# version3.net
KiCad netlist of a schematic drawn in EAGLE
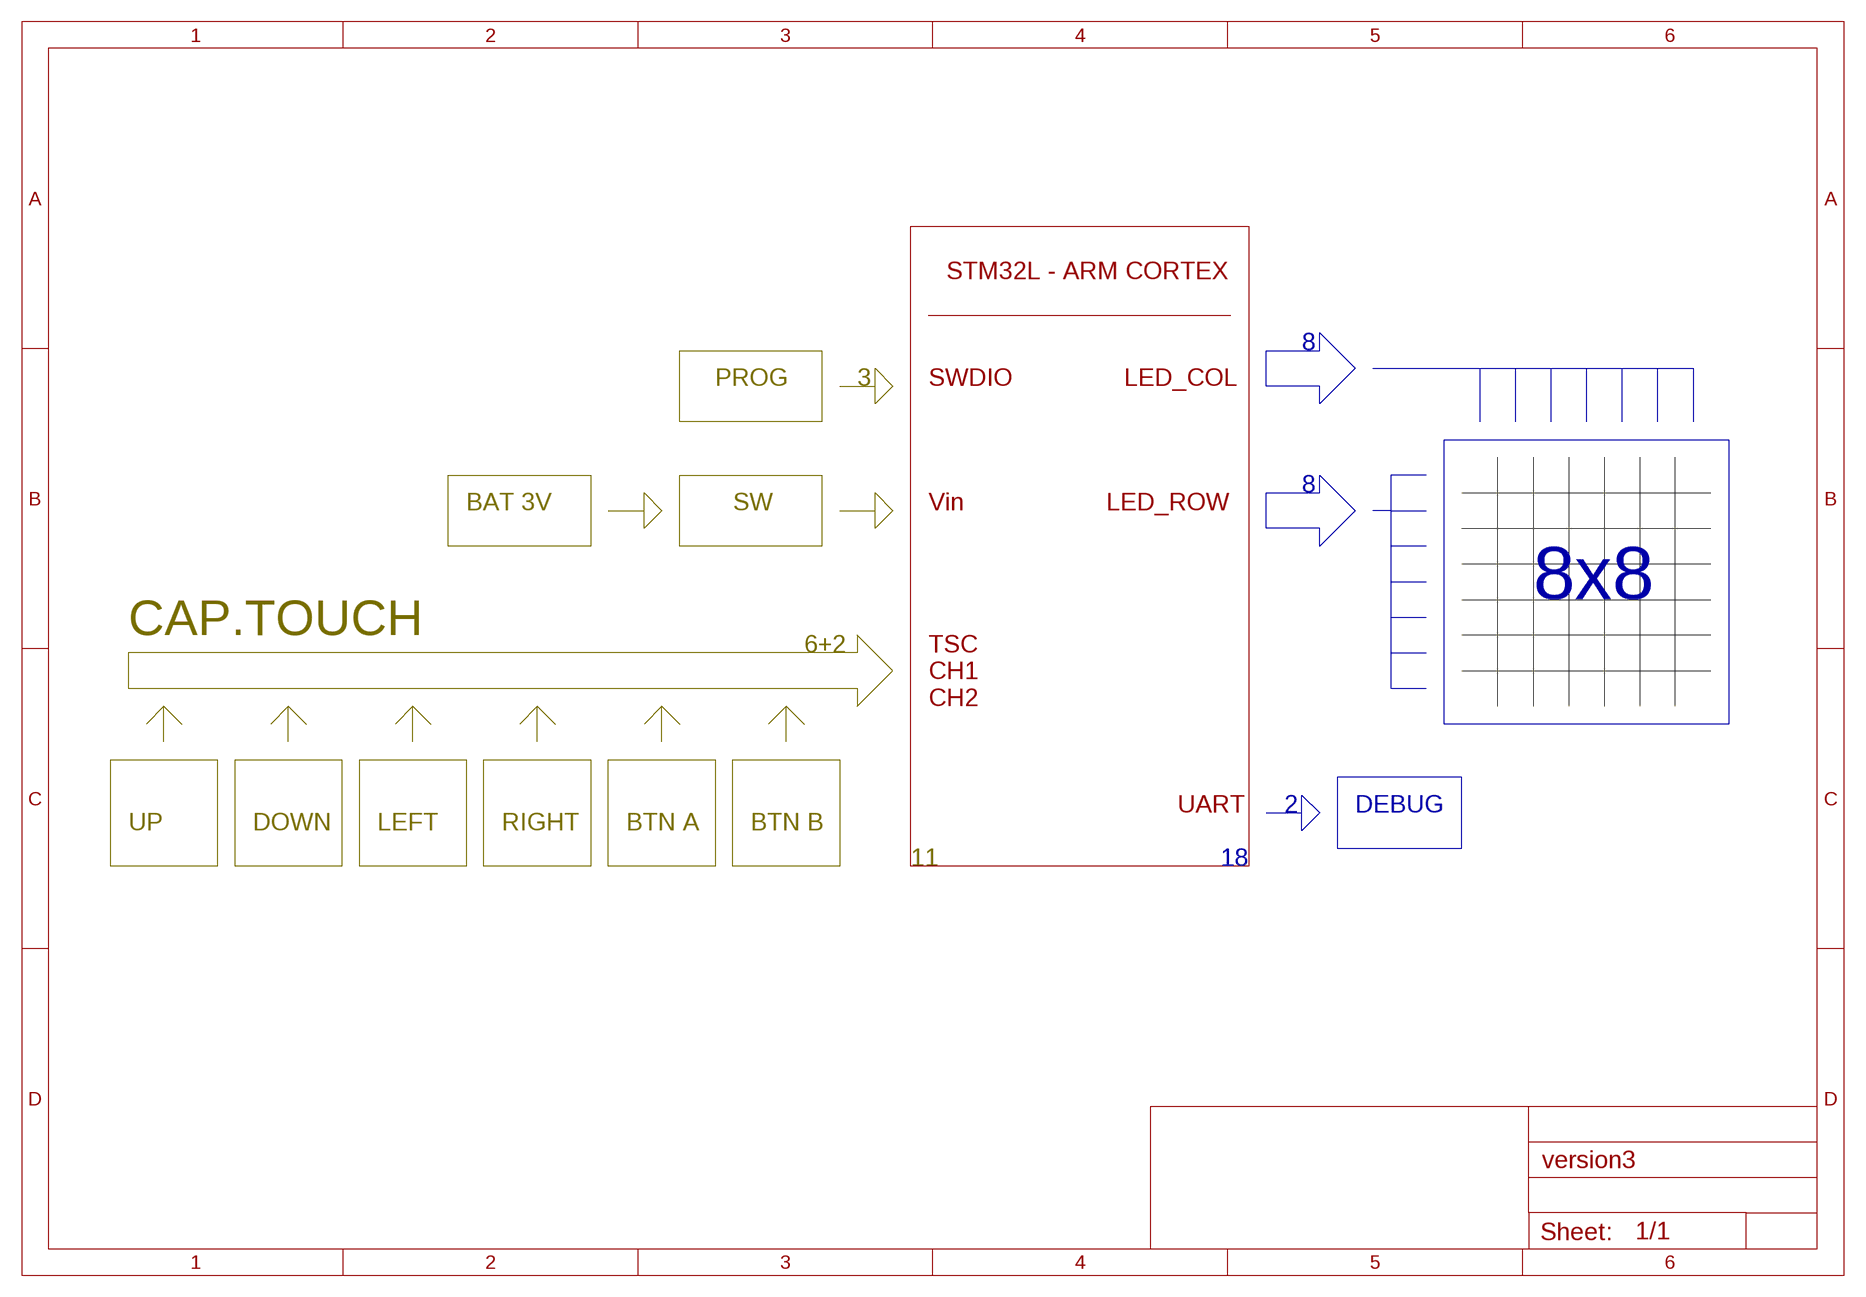
[diagram p0: schematic, sheet 1, part 1 of 2]
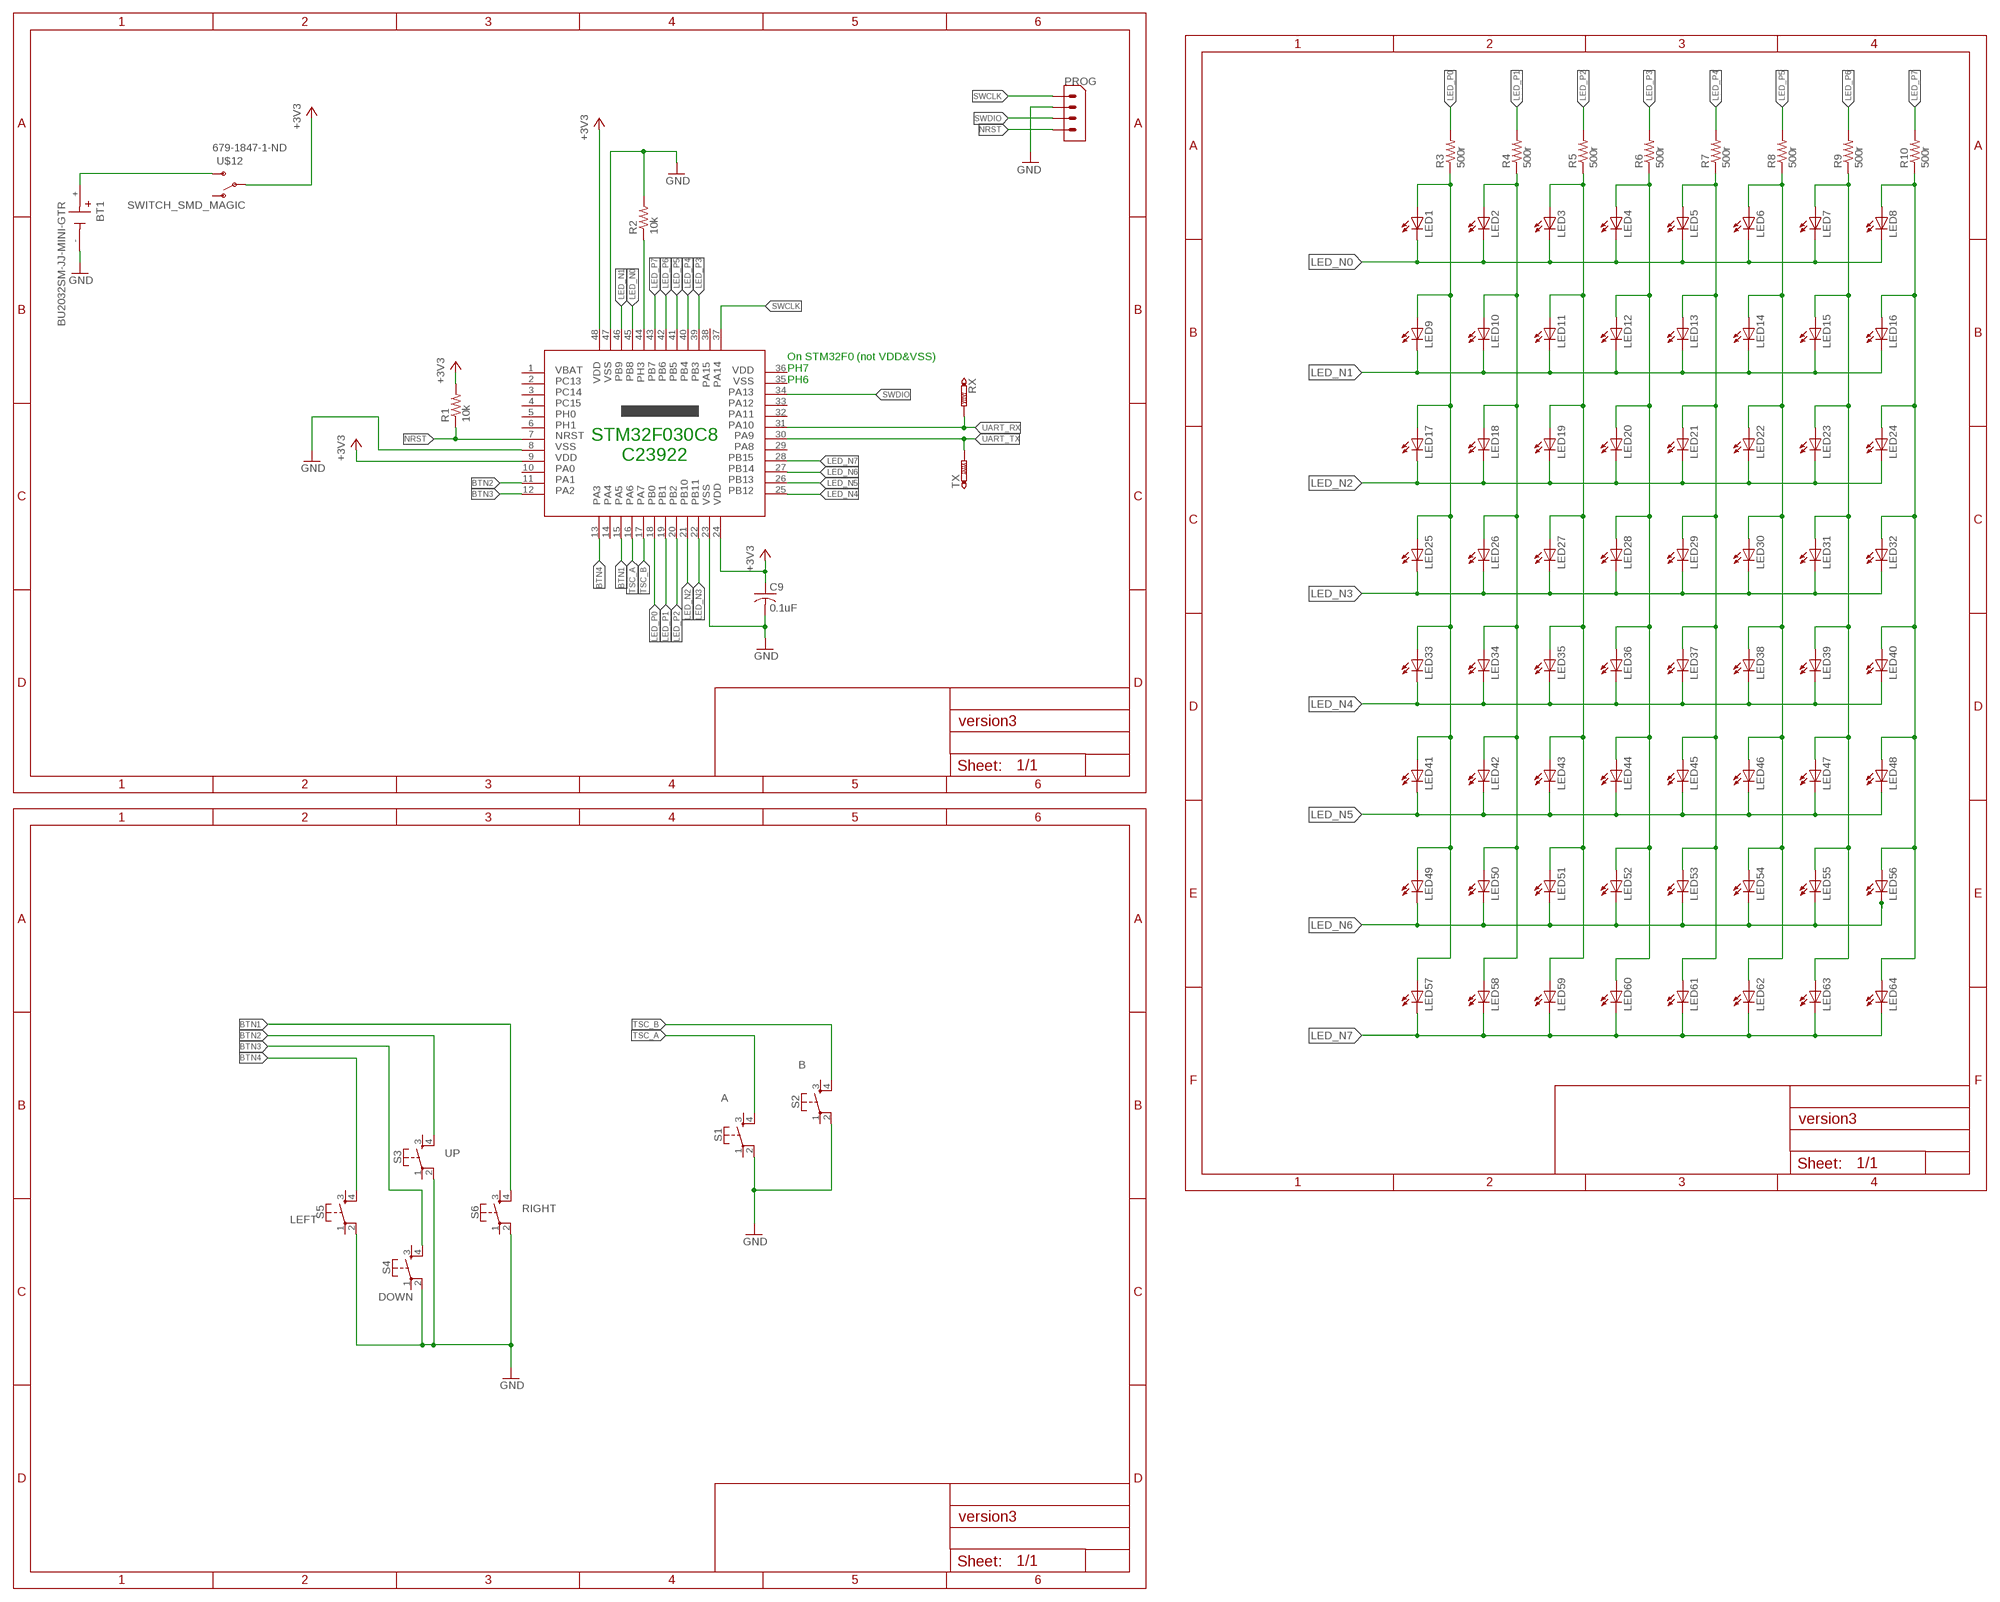
[diagram p1: schematic, sheet 1, part 2 of 2]

(export (version "E")
  (design (tool "Eeschema 10.0.6"))
  (components
    (comp (ref "BT1")
      (value "BU2032SM-JJ-MINI-GTR")
      (footprint "eagle-import:BAT_BU2032SM-JJ-MINI-GTR")
      (fields (field (name "MF") "MPD _Memory"))
      (libsource (lib "eagle-import") (part "BU2032SM-JJ-MINI-GTR"))
    )
    (comp (ref "C9")
      (value "0.1uF")
      (footprint "eagle-import:C0603")
      (libsource (lib "eagle-import") (part "C-USC0603"))
    )
    (comp (ref "LED1")
      (value "LEDCHIP-LED0603")
      (footprint "eagle-import:CHIP-LED0603")
      (libsource (lib "eagle-import") (part "LEDCHIP-LED0603"))
    )
    (comp (ref "LED2")
      (value "LEDCHIP-LED0603")
      (footprint "eagle-import:CHIP-LED0603")
      (libsource (lib "eagle-import") (part "LEDCHIP-LED0603"))
    )
    (comp (ref "LED3")
      (value "LEDCHIP-LED0603")
      (footprint "eagle-import:CHIP-LED0603")
      (libsource (lib "eagle-import") (part "LEDCHIP-LED0603"))
    )
    (comp (ref "LED4")
      (value "LEDCHIP-LED0603")
      (footprint "eagle-import:CHIP-LED0603")
      (libsource (lib "eagle-import") (part "LEDCHIP-LED0603"))
    )
    (comp (ref "LED5")
      (value "LEDCHIP-LED0603")
      (footprint "eagle-import:CHIP-LED0603")
      (libsource (lib "eagle-import") (part "LEDCHIP-LED0603"))
    )
    (comp (ref "LED6")
      (value "LEDCHIP-LED0603")
      (footprint "eagle-import:CHIP-LED0603")
      (libsource (lib "eagle-import") (part "LEDCHIP-LED0603"))
    )
    (comp (ref "LED7")
      (value "LEDCHIP-LED0603")
      (footprint "eagle-import:CHIP-LED0603")
      (libsource (lib "eagle-import") (part "LEDCHIP-LED0603"))
    )
    (comp (ref "LED8")
      (value "LEDCHIP-LED0603")
      (footprint "eagle-import:CHIP-LED0603")
      (libsource (lib "eagle-import") (part "LEDCHIP-LED0603"))
    )
    (comp (ref "LED9")
      (value "LEDCHIP-LED0603")
      (footprint "eagle-import:CHIP-LED0603")
      (libsource (lib "eagle-import") (part "LEDCHIP-LED0603"))
    )
    (comp (ref "LED10")
      (value "LEDCHIP-LED0603")
      (footprint "eagle-import:CHIP-LED0603")
      (libsource (lib "eagle-import") (part "LEDCHIP-LED0603"))
    )
    (comp (ref "LED11")
      (value "LEDCHIP-LED0603")
      (footprint "eagle-import:CHIP-LED0603")
      (libsource (lib "eagle-import") (part "LEDCHIP-LED0603"))
    )
    (comp (ref "LED12")
      (value "LEDCHIP-LED0603")
      (footprint "eagle-import:CHIP-LED0603")
      (libsource (lib "eagle-import") (part "LEDCHIP-LED0603"))
    )
    (comp (ref "LED13")
      (value "LEDCHIP-LED0603")
      (footprint "eagle-import:CHIP-LED0603")
      (libsource (lib "eagle-import") (part "LEDCHIP-LED0603"))
    )
    (comp (ref "LED14")
      (value "LEDCHIP-LED0603")
      (footprint "eagle-import:CHIP-LED0603")
      (libsource (lib "eagle-import") (part "LEDCHIP-LED0603"))
    )
    (comp (ref "LED15")
      (value "LEDCHIP-LED0603")
      (footprint "eagle-import:CHIP-LED0603")
      (libsource (lib "eagle-import") (part "LEDCHIP-LED0603"))
    )
    (comp (ref "LED16")
      (value "LEDCHIP-LED0603")
      (footprint "eagle-import:CHIP-LED0603")
      (libsource (lib "eagle-import") (part "LEDCHIP-LED0603"))
    )
    (comp (ref "LED17")
      (value "LEDCHIP-LED0603")
      (footprint "eagle-import:CHIP-LED0603")
      (libsource (lib "eagle-import") (part "LEDCHIP-LED0603"))
    )
    (comp (ref "LED18")
      (value "LEDCHIP-LED0603")
      (footprint "eagle-import:CHIP-LED0603")
      (libsource (lib "eagle-import") (part "LEDCHIP-LED0603"))
    )
    (comp (ref "LED19")
      (value "LEDCHIP-LED0603")
      (footprint "eagle-import:CHIP-LED0603")
      (libsource (lib "eagle-import") (part "LEDCHIP-LED0603"))
    )
    (comp (ref "LED20")
      (value "LEDCHIP-LED0603")
      (footprint "eagle-import:CHIP-LED0603")
      (libsource (lib "eagle-import") (part "LEDCHIP-LED0603"))
    )
    (comp (ref "LED21")
      (value "LEDCHIP-LED0603")
      (footprint "eagle-import:CHIP-LED0603")
      (libsource (lib "eagle-import") (part "LEDCHIP-LED0603"))
    )
    (comp (ref "LED22")
      (value "LEDCHIP-LED0603")
      (footprint "eagle-import:CHIP-LED0603")
      (libsource (lib "eagle-import") (part "LEDCHIP-LED0603"))
    )
    (comp (ref "LED23")
      (value "LEDCHIP-LED0603")
      (footprint "eagle-import:CHIP-LED0603")
      (libsource (lib "eagle-import") (part "LEDCHIP-LED0603"))
    )
    (comp (ref "LED24")
      (value "LEDCHIP-LED0603")
      (footprint "eagle-import:CHIP-LED0603")
      (libsource (lib "eagle-import") (part "LEDCHIP-LED0603"))
    )
    (comp (ref "LED25")
      (value "LEDCHIP-LED0603")
      (footprint "eagle-import:CHIP-LED0603")
      (libsource (lib "eagle-import") (part "LEDCHIP-LED0603"))
    )
    (comp (ref "LED26")
      (value "LEDCHIP-LED0603")
      (footprint "eagle-import:CHIP-LED0603")
      (libsource (lib "eagle-import") (part "LEDCHIP-LED0603"))
    )
    (comp (ref "LED27")
      (value "LEDCHIP-LED0603")
      (footprint "eagle-import:CHIP-LED0603")
      (libsource (lib "eagle-import") (part "LEDCHIP-LED0603"))
    )
    (comp (ref "LED28")
      (value "LEDCHIP-LED0603")
      (footprint "eagle-import:CHIP-LED0603")
      (libsource (lib "eagle-import") (part "LEDCHIP-LED0603"))
    )
    (comp (ref "LED29")
      (value "LEDCHIP-LED0603")
      (footprint "eagle-import:CHIP-LED0603")
      (libsource (lib "eagle-import") (part "LEDCHIP-LED0603"))
    )
    (comp (ref "LED30")
      (value "LEDCHIP-LED0603")
      (footprint "eagle-import:CHIP-LED0603")
      (libsource (lib "eagle-import") (part "LEDCHIP-LED0603"))
    )
    (comp (ref "LED31")
      (value "LEDCHIP-LED0603")
      (footprint "eagle-import:CHIP-LED0603")
      (libsource (lib "eagle-import") (part "LEDCHIP-LED0603"))
    )
    (comp (ref "LED32")
      (value "LEDCHIP-LED0603")
      (footprint "eagle-import:CHIP-LED0603")
      (libsource (lib "eagle-import") (part "LEDCHIP-LED0603"))
    )
    (comp (ref "LED33")
      (value "LEDCHIP-LED0603")
      (footprint "eagle-import:CHIP-LED0603")
      (libsource (lib "eagle-import") (part "LEDCHIP-LED0603"))
    )
    (comp (ref "LED34")
      (value "LEDCHIP-LED0603")
      (footprint "eagle-import:CHIP-LED0603")
      (libsource (lib "eagle-import") (part "LEDCHIP-LED0603"))
    )
    (comp (ref "LED35")
      (value "LEDCHIP-LED0603")
      (footprint "eagle-import:CHIP-LED0603")
      (libsource (lib "eagle-import") (part "LEDCHIP-LED0603"))
    )
    (comp (ref "LED36")
      (value "LEDCHIP-LED0603")
      (footprint "eagle-import:CHIP-LED0603")
      (libsource (lib "eagle-import") (part "LEDCHIP-LED0603"))
    )
    (comp (ref "LED37")
      (value "LEDCHIP-LED0603")
      (footprint "eagle-import:CHIP-LED0603")
      (libsource (lib "eagle-import") (part "LEDCHIP-LED0603"))
    )
    (comp (ref "LED38")
      (value "LEDCHIP-LED0603")
      (footprint "eagle-import:CHIP-LED0603")
      (libsource (lib "eagle-import") (part "LEDCHIP-LED0603"))
    )
    (comp (ref "LED39")
      (value "LEDCHIP-LED0603")
      (footprint "eagle-import:CHIP-LED0603")
      (libsource (lib "eagle-import") (part "LEDCHIP-LED0603"))
    )
    (comp (ref "LED40")
      (value "LEDCHIP-LED0603")
      (footprint "eagle-import:CHIP-LED0603")
      (libsource (lib "eagle-import") (part "LEDCHIP-LED0603"))
    )
    (comp (ref "LED41")
      (value "LEDCHIP-LED0603")
      (footprint "eagle-import:CHIP-LED0603")
      (libsource (lib "eagle-import") (part "LEDCHIP-LED0603"))
    )
    (comp (ref "LED42")
      (value "LEDCHIP-LED0603")
      (footprint "eagle-import:CHIP-LED0603")
      (libsource (lib "eagle-import") (part "LEDCHIP-LED0603"))
    )
    (comp (ref "LED43")
      (value "LEDCHIP-LED0603")
      (footprint "eagle-import:CHIP-LED0603")
      (libsource (lib "eagle-import") (part "LEDCHIP-LED0603"))
    )
    (comp (ref "LED44")
      (value "LEDCHIP-LED0603")
      (footprint "eagle-import:CHIP-LED0603")
      (libsource (lib "eagle-import") (part "LEDCHIP-LED0603"))
    )
    (comp (ref "LED45")
      (value "LEDCHIP-LED0603")
      (footprint "eagle-import:CHIP-LED0603")
      (libsource (lib "eagle-import") (part "LEDCHIP-LED0603"))
    )
    (comp (ref "LED46")
      (value "LEDCHIP-LED0603")
      (footprint "eagle-import:CHIP-LED0603")
      (libsource (lib "eagle-import") (part "LEDCHIP-LED0603"))
    )
    (comp (ref "LED47")
      (value "LEDCHIP-LED0603")
      (footprint "eagle-import:CHIP-LED0603")
      (libsource (lib "eagle-import") (part "LEDCHIP-LED0603"))
    )
    (comp (ref "LED48")
      (value "LEDCHIP-LED0603")
      (footprint "eagle-import:CHIP-LED0603")
      (libsource (lib "eagle-import") (part "LEDCHIP-LED0603"))
    )
    (comp (ref "LED49")
      (value "LEDCHIP-LED0603")
      (footprint "eagle-import:CHIP-LED0603")
      (libsource (lib "eagle-import") (part "LEDCHIP-LED0603"))
    )
    (comp (ref "LED50")
      (value "LEDCHIP-LED0603")
      (footprint "eagle-import:CHIP-LED0603")
      (libsource (lib "eagle-import") (part "LEDCHIP-LED0603"))
    )
    (comp (ref "LED51")
      (value "LEDCHIP-LED0603")
      (footprint "eagle-import:CHIP-LED0603")
      (libsource (lib "eagle-import") (part "LEDCHIP-LED0603"))
    )
    (comp (ref "LED52")
      (value "LEDCHIP-LED0603")
      (footprint "eagle-import:CHIP-LED0603")
      (libsource (lib "eagle-import") (part "LEDCHIP-LED0603"))
    )
    (comp (ref "LED53")
      (value "LEDCHIP-LED0603")
      (footprint "eagle-import:CHIP-LED0603")
      (libsource (lib "eagle-import") (part "LEDCHIP-LED0603"))
    )
    (comp (ref "LED54")
      (value "LEDCHIP-LED0603")
      (footprint "eagle-import:CHIP-LED0603")
      (libsource (lib "eagle-import") (part "LEDCHIP-LED0603"))
    )
    (comp (ref "LED55")
      (value "LEDCHIP-LED0603")
      (footprint "eagle-import:CHIP-LED0603")
      (libsource (lib "eagle-import") (part "LEDCHIP-LED0603"))
    )
    (comp (ref "LED56")
      (value "LEDCHIP-LED0603")
      (footprint "eagle-import:CHIP-LED0603")
      (libsource (lib "eagle-import") (part "LEDCHIP-LED0603"))
    )
    (comp (ref "LED57")
      (value "LEDCHIP-LED0603")
      (footprint "eagle-import:CHIP-LED0603")
      (libsource (lib "eagle-import") (part "LEDCHIP-LED0603"))
    )
    (comp (ref "LED58")
      (value "LEDCHIP-LED0603")
      (footprint "eagle-import:CHIP-LED0603")
      (libsource (lib "eagle-import") (part "LEDCHIP-LED0603"))
    )
    (comp (ref "LED59")
      (value "LEDCHIP-LED0603")
      (footprint "eagle-import:CHIP-LED0603")
      (libsource (lib "eagle-import") (part "LEDCHIP-LED0603"))
    )
    (comp (ref "LED60")
      (value "LEDCHIP-LED0603")
      (footprint "eagle-import:CHIP-LED0603")
      (libsource (lib "eagle-import") (part "LEDCHIP-LED0603"))
    )
    (comp (ref "LED61")
      (value "LEDCHIP-LED0603")
      (footprint "eagle-import:CHIP-LED0603")
      (libsource (lib "eagle-import") (part "LEDCHIP-LED0603"))
    )
    (comp (ref "LED62")
      (value "LEDCHIP-LED0603")
      (footprint "eagle-import:CHIP-LED0603")
      (libsource (lib "eagle-import") (part "LEDCHIP-LED0603"))
    )
    (comp (ref "LED63")
      (value "LEDCHIP-LED0603")
      (footprint "eagle-import:CHIP-LED0603")
      (libsource (lib "eagle-import") (part "LEDCHIP-LED0603"))
    )
    (comp (ref "LED64")
      (value "LEDCHIP-LED0603")
      (footprint "eagle-import:CHIP-LED0603")
      (libsource (lib "eagle-import") (part "LEDCHIP-LED0603"))
    )
    (comp (ref "PROG")
      (value "4-PIN-1.25MM")
      (footprint "eagle-import:4-PIN-1.25MM")
      (libsource (lib "eagle-import") (part "4-PIN-1.25MM"))
    )
    (comp (ref "R1")
      (value "10k")
      (footprint "eagle-import:R0603")
      (libsource (lib "eagle-import") (part "R-US_R0603"))
    )
    (comp (ref "R2")
      (value "10k")
      (footprint "eagle-import:R0603")
      (libsource (lib "eagle-import") (part "R-US_R0603"))
    )
    (comp (ref "R3")
      (value "500r")
      (footprint "eagle-import:R0603")
      (libsource (lib "eagle-import") (part "R-US_R0603"))
    )
    (comp (ref "R4")
      (value "500r")
      (footprint "eagle-import:R0603")
      (libsource (lib "eagle-import") (part "R-US_R0603"))
    )
    (comp (ref "R5")
      (value "500r")
      (footprint "eagle-import:R0603")
      (libsource (lib "eagle-import") (part "R-US_R0603"))
    )
    (comp (ref "R6")
      (value "500r")
      (footprint "eagle-import:R0603")
      (libsource (lib "eagle-import") (part "R-US_R0603"))
    )
    (comp (ref "R7")
      (value "500r")
      (footprint "eagle-import:R0603")
      (libsource (lib "eagle-import") (part "R-US_R0603"))
    )
    (comp (ref "R8")
      (value "500r")
      (footprint "eagle-import:R0603")
      (libsource (lib "eagle-import") (part "R-US_R0603"))
    )
    (comp (ref "R9")
      (value "500r")
      (footprint "eagle-import:R0603")
      (libsource (lib "eagle-import") (part "R-US_R0603"))
    )
    (comp (ref "R10")
      (value "500r")
      (footprint "eagle-import:R0603")
      (libsource (lib "eagle-import") (part "R-US_R0603"))
    )
    (comp (ref "RX")
      (value "PTR1B1,27")
      (footprint "eagle-import:B1,27")
      (libsource (lib "eagle-import") (part "PTR1B1,27"))
    )
    (comp (ref "S1")
      (value "MOMENTARY-SWITCH-SPST-2-SMD-5.2MM")
      (footprint "eagle-import:TACTILE_SWITCH_SMD_5.2MM")
      (libsource (lib "eagle-import") (part "MOMENTARY-SWITCH-SPST-2-SMD-5.2MM"))
    )
    (comp (ref "S2")
      (value "MOMENTARY-SWITCH-SPST-2-SMD-5.2MM")
      (footprint "eagle-import:TACTILE_SWITCH_SMD_5.2MM")
      (libsource (lib "eagle-import") (part "MOMENTARY-SWITCH-SPST-2-SMD-5.2MM"))
    )
    (comp (ref "S3")
      (value "MOMENTARY-SWITCH-SPST-2-SMD-5.2MM")
      (footprint "eagle-import:TACTILE_SWITCH_SMD_5.2MM")
      (libsource (lib "eagle-import") (part "MOMENTARY-SWITCH-SPST-2-SMD-5.2MM"))
    )
    (comp (ref "S4")
      (value "MOMENTARY-SWITCH-SPST-2-SMD-5.2MM")
      (footprint "eagle-import:TACTILE_SWITCH_SMD_5.2MM")
      (libsource (lib "eagle-import") (part "MOMENTARY-SWITCH-SPST-2-SMD-5.2MM"))
    )
    (comp (ref "S5")
      (value "MOMENTARY-SWITCH-SPST-2-SMD-5.2MM")
      (footprint "eagle-import:TACTILE_SWITCH_SMD_5.2MM")
      (libsource (lib "eagle-import") (part "MOMENTARY-SWITCH-SPST-2-SMD-5.2MM"))
    )
    (comp (ref "S6")
      (value "MOMENTARY-SWITCH-SPST-2-SMD-5.2MM")
      (footprint "eagle-import:TACTILE_SWITCH_SMD_5.2MM")
      (libsource (lib "eagle-import") (part "MOMENTARY-SWITCH-SPST-2-SMD-5.2MM"))
    )
    (comp (ref "TX")
      (value "PTR1B1,27")
      (footprint "eagle-import:B1,27")
      (libsource (lib "eagle-import") (part "PTR1B1,27"))
    )
    (comp (ref "U$2")
      (value "STM32L431CC")
      (footprint "eagle-import:QFP50P900X900X160-48")
      (libsource (lib "eagle-import") (part "STM32L431CC"))
    )
    (comp (ref "U$12")
      (value "SWITCH_SMD_MAGIC")
      (footprint "eagle-import:SWITCH_SMD_SUNKEN")
      (libsource (lib "eagle-import") (part "SWITCH_SMD_MAGIC"))
    )
  )
  (nets
    (net (code "1") (name "+3V3") (class "Default")
      (node (ref "C9") (pin "1") (pinfunction "1_1") (pintype "passive"))
      (node (ref "R1") (pin "2") (pinfunction "2_2") (pintype "passive"))
      (node (ref "U$12") (pin "2") (pinfunction "P_2") (pintype "passive"))
      (node (ref "U$2") (pin "24") (pinfunction "P$24_24") (pintype "bidirectional"))
      (node (ref "U$2") (pin "48") (pinfunction "P$48_48") (pintype "bidirectional"))
      (node (ref "U$2") (pin "9") (pinfunction "P$9_9") (pintype "bidirectional"))
    )
    (net (code "2") (name "BTN1") (class "Default")
      (node (ref "S6") (pin "4") (pinfunction "4_4") (pintype "passive"))
      (node (ref "U$2") (pin "15") (pinfunction "P$15_15") (pintype "bidirectional"))
    )
    (net (code "3") (name "BTN2") (class "Default")
      (node (ref "S3") (pin "4") (pinfunction "4_4") (pintype "passive"))
      (node (ref "U$2") (pin "11") (pinfunction "P$11_11") (pintype "bidirectional"))
    )
    (net (code "4") (name "BTN3") (class "Default")
      (node (ref "S4") (pin "4") (pinfunction "4_4") (pintype "passive"))
      (node (ref "U$2") (pin "12") (pinfunction "P$12_12") (pintype "bidirectional"))
    )
    (net (code "5") (name "BTN4") (class "Default")
      (node (ref "S5") (pin "4") (pinfunction "4_4") (pintype "passive"))
      (node (ref "U$2") (pin "13") (pinfunction "P$13_13") (pintype "bidirectional"))
    )
    (net (code "6") (name "GND") (class "Default")
      (node (ref "BT1") (pin "-") (pinfunction "-_-") (pintype "passive"))
      (node (ref "C9") (pin "2") (pinfunction "2_2") (pintype "passive"))
      (node (ref "PROG") (pin "P$3") (pinfunction "2_P$3") (pintype "bidirectional"))
      (node (ref "R2") (pin "2") (pinfunction "2_2") (pintype "passive"))
      (node (ref "S1") (pin "2") (pinfunction "2_2") (pintype "passive"))
      (node (ref "S2") (pin "2") (pinfunction "2_2") (pintype "passive"))
      (node (ref "S3") (pin "2") (pinfunction "2_2") (pintype "passive"))
      (node (ref "S4") (pin "2") (pinfunction "2_2") (pintype "passive"))
      (node (ref "S5") (pin "2") (pinfunction "2_2") (pintype "passive"))
      (node (ref "S6") (pin "2") (pinfunction "2_2") (pintype "passive"))
      (node (ref "U$2") (pin "23") (pinfunction "P$23_23") (pintype "bidirectional"))
      (node (ref "U$2") (pin "47") (pinfunction "P$47_47") (pintype "bidirectional"))
      (node (ref "U$2") (pin "8") (pinfunction "P$8_8") (pintype "bidirectional"))
    )
    (net (code "7") (name "LED_N0") (class "Default")
      (node (ref "LED1") (pin "C") (pinfunction "C_C") (pintype "passive"))
      (node (ref "LED2") (pin "C") (pinfunction "C_C") (pintype "passive"))
      (node (ref "LED3") (pin "C") (pinfunction "C_C") (pintype "passive"))
      (node (ref "LED4") (pin "C") (pinfunction "C_C") (pintype "passive"))
      (node (ref "LED5") (pin "C") (pinfunction "C_C") (pintype "passive"))
      (node (ref "LED6") (pin "C") (pinfunction "C_C") (pintype "passive"))
      (node (ref "LED7") (pin "C") (pinfunction "C_C") (pintype "passive"))
      (node (ref "LED8") (pin "C") (pinfunction "C_C") (pintype "passive"))
      (node (ref "U$2") (pin "45") (pinfunction "P$45_45") (pintype "bidirectional"))
    )
    (net (code "8") (name "LED_N1") (class "Default")
      (node (ref "LED10") (pin "C") (pinfunction "C_C") (pintype "passive"))
      (node (ref "LED11") (pin "C") (pinfunction "C_C") (pintype "passive"))
      (node (ref "LED12") (pin "C") (pinfunction "C_C") (pintype "passive"))
      (node (ref "LED13") (pin "C") (pinfunction "C_C") (pintype "passive"))
      (node (ref "LED14") (pin "C") (pinfunction "C_C") (pintype "passive"))
      (node (ref "LED15") (pin "C") (pinfunction "C_C") (pintype "passive"))
      (node (ref "LED16") (pin "C") (pinfunction "C_C") (pintype "passive"))
      (node (ref "LED9") (pin "C") (pinfunction "C_C") (pintype "passive"))
      (node (ref "U$2") (pin "46") (pinfunction "P$46_46") (pintype "bidirectional"))
    )
    (net (code "9") (name "LED_N2") (class "Default")
      (node (ref "LED17") (pin "C") (pinfunction "C_C") (pintype "passive"))
      (node (ref "LED18") (pin "C") (pinfunction "C_C") (pintype "passive"))
      (node (ref "LED19") (pin "C") (pinfunction "C_C") (pintype "passive"))
      (node (ref "LED20") (pin "C") (pinfunction "C_C") (pintype "passive"))
      (node (ref "LED21") (pin "C") (pinfunction "C_C") (pintype "passive"))
      (node (ref "LED22") (pin "C") (pinfunction "C_C") (pintype "passive"))
      (node (ref "LED23") (pin "C") (pinfunction "C_C") (pintype "passive"))
      (node (ref "LED24") (pin "C") (pinfunction "C_C") (pintype "passive"))
      (node (ref "U$2") (pin "21") (pinfunction "P$21_21") (pintype "bidirectional"))
    )
    (net (code "10") (name "LED_N3") (class "Default")
      (node (ref "LED25") (pin "C") (pinfunction "C_C") (pintype "passive"))
      (node (ref "LED26") (pin "C") (pinfunction "C_C") (pintype "passive"))
      (node (ref "LED27") (pin "C") (pinfunction "C_C") (pintype "passive"))
      (node (ref "LED28") (pin "C") (pinfunction "C_C") (pintype "passive"))
      (node (ref "LED29") (pin "C") (pinfunction "C_C") (pintype "passive"))
      (node (ref "LED30") (pin "C") (pinfunction "C_C") (pintype "passive"))
      (node (ref "LED31") (pin "C") (pinfunction "C_C") (pintype "passive"))
      (node (ref "LED32") (pin "C") (pinfunction "C_C") (pintype "passive"))
      (node (ref "U$2") (pin "22") (pinfunction "P$22_22") (pintype "bidirectional"))
    )
    (net (code "11") (name "LED_N4") (class "Default")
      (node (ref "LED33") (pin "C") (pinfunction "C_C") (pintype "passive"))
      (node (ref "LED34") (pin "C") (pinfunction "C_C") (pintype "passive"))
      (node (ref "LED35") (pin "C") (pinfunction "C_C") (pintype "passive"))
      (node (ref "LED36") (pin "C") (pinfunction "C_C") (pintype "passive"))
      (node (ref "LED37") (pin "C") (pinfunction "C_C") (pintype "passive"))
      (node (ref "LED38") (pin "C") (pinfunction "C_C") (pintype "passive"))
      (node (ref "LED39") (pin "C") (pinfunction "C_C") (pintype "passive"))
      (node (ref "LED40") (pin "C") (pinfunction "C_C") (pintype "passive"))
      (node (ref "U$2") (pin "25") (pinfunction "P$25_25") (pintype "bidirectional"))
    )
    (net (code "12") (name "LED_N5") (class "Default")
      (node (ref "LED41") (pin "C") (pinfunction "C_C") (pintype "passive"))
      (node (ref "LED42") (pin "C") (pinfunction "C_C") (pintype "passive"))
      (node (ref "LED43") (pin "C") (pinfunction "C_C") (pintype "passive"))
      (node (ref "LED44") (pin "C") (pinfunction "C_C") (pintype "passive"))
      (node (ref "LED45") (pin "C") (pinfunction "C_C") (pintype "passive"))
      (node (ref "LED46") (pin "C") (pinfunction "C_C") (pintype "passive"))
      (node (ref "LED47") (pin "C") (pinfunction "C_C") (pintype "passive"))
      (node (ref "LED48") (pin "C") (pinfunction "C_C") (pintype "passive"))
      (node (ref "U$2") (pin "26") (pinfunction "P$26_26") (pintype "bidirectional"))
    )
    (net (code "13") (name "LED_N6") (class "Default")
      (node (ref "LED49") (pin "C") (pinfunction "C_C") (pintype "passive"))
      (node (ref "LED50") (pin "C") (pinfunction "C_C") (pintype "passive"))
      (node (ref "LED51") (pin "C") (pinfunction "C_C") (pintype "passive"))
      (node (ref "LED52") (pin "C") (pinfunction "C_C") (pintype "passive"))
      (node (ref "LED53") (pin "C") (pinfunction "C_C") (pintype "passive"))
      (node (ref "LED54") (pin "C") (pinfunction "C_C") (pintype "passive"))
      (node (ref "LED55") (pin "C") (pinfunction "C_C") (pintype "passive"))
      (node (ref "LED56") (pin "C") (pinfunction "C_C") (pintype "passive"))
      (node (ref "U$2") (pin "27") (pinfunction "P$27_27") (pintype "bidirectional"))
    )
    (net (code "14") (name "LED_N7") (class "Default")
      (node (ref "LED57") (pin "C") (pinfunction "C_C") (pintype "passive"))
      (node (ref "LED58") (pin "C") (pinfunction "C_C") (pintype "passive"))
      (node (ref "LED59") (pin "C") (pinfunction "C_C") (pintype "passive"))
      (node (ref "LED60") (pin "C") (pinfunction "C_C") (pintype "passive"))
      (node (ref "LED61") (pin "C") (pinfunction "C_C") (pintype "passive"))
      (node (ref "LED62") (pin "C") (pinfunction "C_C") (pintype "passive"))
      (node (ref "LED63") (pin "C") (pinfunction "C_C") (pintype "passive"))
      (node (ref "LED64") (pin "C") (pinfunction "C_C") (pintype "passive"))
      (node (ref "U$2") (pin "28") (pinfunction "P$28_28") (pintype "bidirectional"))
    )
    (net (code "15") (name "LED_P0") (class "Default")
      (node (ref "R3") (pin "2") (pinfunction "2_2") (pintype "passive"))
      (node (ref "U$2") (pin "18") (pinfunction "P$18_18") (pintype "bidirectional"))
    )
    (net (code "16") (name "LED_P1") (class "Default")
      (node (ref "R4") (pin "2") (pinfunction "2_2") (pintype "passive"))
      (node (ref "U$2") (pin "19") (pinfunction "P$19_19") (pintype "bidirectional"))
    )
    (net (code "17") (name "LED_P2") (class "Default")
      (node (ref "R5") (pin "2") (pinfunction "2_2") (pintype "passive"))
      (node (ref "U$2") (pin "20") (pinfunction "P$20_20") (pintype "bidirectional"))
    )
    (net (code "18") (name "LED_P3") (class "Default")
      (node (ref "R6") (pin "2") (pinfunction "2_2") (pintype "passive"))
      (node (ref "U$2") (pin "39") (pinfunction "P$39_39") (pintype "bidirectional"))
    )
    (net (code "19") (name "LED_P4") (class "Default")
      (node (ref "R7") (pin "2") (pinfunction "2_2") (pintype "passive"))
      (node (ref "U$2") (pin "40") (pinfunction "P$40_40") (pintype "bidirectional"))
    )
    (net (code "20") (name "LED_P5") (class "Default")
      (node (ref "R8") (pin "2") (pinfunction "2_2") (pintype "passive"))
      (node (ref "U$2") (pin "41") (pinfunction "P$41_41") (pintype "bidirectional"))
    )
    (net (code "21") (name "LED_P6") (class "Default")
      (node (ref "R9") (pin "2") (pinfunction "2_2") (pintype "passive"))
      (node (ref "U$2") (pin "42") (pinfunction "P$42_42") (pintype "bidirectional"))
    )
    (net (code "22") (name "LED_P7") (class "Default")
      (node (ref "R10") (pin "2") (pinfunction "2_2") (pintype "passive"))
      (node (ref "U$2") (pin "43") (pinfunction "P$43_43") (pintype "bidirectional"))
    )
    (net (code "23") (name "NRST") (class "Default")
      (node (ref "PROG") (pin "P$1") (pinfunction "4_P$1") (pintype "bidirectional"))
      (node (ref "R1") (pin "1") (pinfunction "1_1") (pintype "passive"))
      (node (ref "U$2") (pin "7") (pinfunction "P$7_7") (pintype "bidirectional"))
    )
    (net (code "24") (name "Net-(LED1-PadA)") (class "Default")
      (node (ref "LED1") (pin "A") (pinfunction "A_A") (pintype "passive"))
      (node (ref "LED17") (pin "A") (pinfunction "A_A") (pintype "passive"))
      (node (ref "LED25") (pin "A") (pinfunction "A_A") (pintype "passive"))
      (node (ref "LED33") (pin "A") (pinfunction "A_A") (pintype "passive"))
      (node (ref "LED41") (pin "A") (pinfunction "A_A") (pintype "passive"))
      (node (ref "LED49") (pin "A") (pinfunction "A_A") (pintype "passive"))
      (node (ref "LED57") (pin "A") (pinfunction "A_A") (pintype "passive"))
      (node (ref "LED9") (pin "A") (pinfunction "A_A") (pintype "passive"))
      (node (ref "R3") (pin "1") (pinfunction "1_1") (pintype "passive"))
    )
    (net (code "25") (name "Net-(LED10-PadA)") (class "Default")
      (node (ref "LED10") (pin "A") (pinfunction "A_A") (pintype "passive"))
      (node (ref "LED18") (pin "A") (pinfunction "A_A") (pintype "passive"))
      (node (ref "LED2") (pin "A") (pinfunction "A_A") (pintype "passive"))
      (node (ref "LED26") (pin "A") (pinfunction "A_A") (pintype "passive"))
      (node (ref "LED34") (pin "A") (pinfunction "A_A") (pintype "passive"))
      (node (ref "LED42") (pin "A") (pinfunction "A_A") (pintype "passive"))
      (node (ref "LED50") (pin "A") (pinfunction "A_A") (pintype "passive"))
      (node (ref "LED58") (pin "A") (pinfunction "A_A") (pintype "passive"))
      (node (ref "R4") (pin "1") (pinfunction "1_1") (pintype "passive"))
    )
    (net (code "26") (name "Net-(LED11-PadA)") (class "Default")
      (node (ref "LED11") (pin "A") (pinfunction "A_A") (pintype "passive"))
      (node (ref "LED19") (pin "A") (pinfunction "A_A") (pintype "passive"))
      (node (ref "LED27") (pin "A") (pinfunction "A_A") (pintype "passive"))
      (node (ref "LED3") (pin "A") (pinfunction "A_A") (pintype "passive"))
      (node (ref "LED35") (pin "A") (pinfunction "A_A") (pintype "passive"))
      (node (ref "LED43") (pin "A") (pinfunction "A_A") (pintype "passive"))
      (node (ref "LED51") (pin "A") (pinfunction "A_A") (pintype "passive"))
      (node (ref "LED59") (pin "A") (pinfunction "A_A") (pintype "passive"))
      (node (ref "R5") (pin "1") (pinfunction "1_1") (pintype "passive"))
    )
    (net (code "27") (name "Net-(LED12-PadA)") (class "Default")
      (node (ref "LED12") (pin "A") (pinfunction "A_A") (pintype "passive"))
      (node (ref "LED20") (pin "A") (pinfunction "A_A") (pintype "passive"))
      (node (ref "LED28") (pin "A") (pinfunction "A_A") (pintype "passive"))
      (node (ref "LED36") (pin "A") (pinfunction "A_A") (pintype "passive"))
      (node (ref "LED4") (pin "A") (pinfunction "A_A") (pintype "passive"))
      (node (ref "LED44") (pin "A") (pinfunction "A_A") (pintype "passive"))
      (node (ref "LED52") (pin "A") (pinfunction "A_A") (pintype "passive"))
      (node (ref "LED60") (pin "A") (pinfunction "A_A") (pintype "passive"))
      (node (ref "R6") (pin "1") (pinfunction "1_1") (pintype "passive"))
    )
    (net (code "28") (name "Net-(LED13-PadA)") (class "Default")
      (node (ref "LED13") (pin "A") (pinfunction "A_A") (pintype "passive"))
      (node (ref "LED21") (pin "A") (pinfunction "A_A") (pintype "passive"))
      (node (ref "LED29") (pin "A") (pinfunction "A_A") (pintype "passive"))
      (node (ref "LED37") (pin "A") (pinfunction "A_A") (pintype "passive"))
      (node (ref "LED45") (pin "A") (pinfunction "A_A") (pintype "passive"))
      (node (ref "LED5") (pin "A") (pinfunction "A_A") (pintype "passive"))
      (node (ref "LED53") (pin "A") (pinfunction "A_A") (pintype "passive"))
      (node (ref "LED61") (pin "A") (pinfunction "A_A") (pintype "passive"))
      (node (ref "R7") (pin "1") (pinfunction "1_1") (pintype "passive"))
    )
    (net (code "29") (name "Net-(LED14-PadA)") (class "Default")
      (node (ref "LED14") (pin "A") (pinfunction "A_A") (pintype "passive"))
      (node (ref "LED22") (pin "A") (pinfunction "A_A") (pintype "passive"))
      (node (ref "LED30") (pin "A") (pinfunction "A_A") (pintype "passive"))
      (node (ref "LED38") (pin "A") (pinfunction "A_A") (pintype "passive"))
      (node (ref "LED46") (pin "A") (pinfunction "A_A") (pintype "passive"))
      (node (ref "LED54") (pin "A") (pinfunction "A_A") (pintype "passive"))
      (node (ref "LED6") (pin "A") (pinfunction "A_A") (pintype "passive"))
      (node (ref "LED62") (pin "A") (pinfunction "A_A") (pintype "passive"))
      (node (ref "R8") (pin "1") (pinfunction "1_1") (pintype "passive"))
    )
    (net (code "30") (name "Net-(LED15-PadA)") (class "Default")
      (node (ref "LED15") (pin "A") (pinfunction "A_A") (pintype "passive"))
      (node (ref "LED23") (pin "A") (pinfunction "A_A") (pintype "passive"))
      (node (ref "LED31") (pin "A") (pinfunction "A_A") (pintype "passive"))
      (node (ref "LED39") (pin "A") (pinfunction "A_A") (pintype "passive"))
      (node (ref "LED47") (pin "A") (pinfunction "A_A") (pintype "passive"))
      (node (ref "LED55") (pin "A") (pinfunction "A_A") (pintype "passive"))
      (node (ref "LED63") (pin "A") (pinfunction "A_A") (pintype "passive"))
      (node (ref "LED7") (pin "A") (pinfunction "A_A") (pintype "passive"))
      (node (ref "R9") (pin "1") (pinfunction "1_1") (pintype "passive"))
    )
    (net (code "31") (name "Net-(LED16-PadA)") (class "Default")
      (node (ref "LED16") (pin "A") (pinfunction "A_A") (pintype "passive"))
      (node (ref "LED24") (pin "A") (pinfunction "A_A") (pintype "passive"))
      (node (ref "LED32") (pin "A") (pinfunction "A_A") (pintype "passive"))
      (node (ref "LED40") (pin "A") (pinfunction "A_A") (pintype "passive"))
      (node (ref "LED48") (pin "A") (pinfunction "A_A") (pintype "passive"))
      (node (ref "LED56") (pin "A") (pinfunction "A_A") (pintype "passive"))
      (node (ref "LED64") (pin "A") (pinfunction "A_A") (pintype "passive"))
      (node (ref "LED8") (pin "A") (pinfunction "A_A") (pintype "passive"))
      (node (ref "R10") (pin "1") (pinfunction "1_1") (pintype "passive"))
    )
    (net (code "32") (name "Net-(U$2-P$44)") (class "Default")
      (node (ref "R2") (pin "1") (pinfunction "1_1") (pintype "passive"))
      (node (ref "U$2") (pin "44") (pinfunction "P$44_44") (pintype "bidirectional"))
    )
    (net (code "33") (name "Net-(U$12-S)") (class "Default")
      (node (ref "BT1") (pin "+") (pinfunction "+_+") (pintype "passive"))
      (node (ref "U$12") (pin "3") (pinfunction "S_3") (pintype "passive"))
    )
    (net (code "34") (name "SWCLK") (class "Default")
      (node (ref "PROG") (pin "P$4") (pinfunction "1_P$4") (pintype "bidirectional"))
      (node (ref "U$2") (pin "37") (pinfunction "P$37_37") (pintype "bidirectional"))
    )
    (net (code "35") (name "SWDIO") (class "Default")
      (node (ref "PROG") (pin "P$2") (pinfunction "3_P$2") (pintype "bidirectional"))
      (node (ref "U$2") (pin "34") (pinfunction "P$34_34") (pintype "bidirectional"))
    )
    (net (code "36") (name "TSC_A") (class "Default")
      (node (ref "S1") (pin "4") (pinfunction "4_4") (pintype "passive"))
      (node (ref "U$2") (pin "16") (pinfunction "P$16_16") (pintype "bidirectional"))
    )
    (net (code "37") (name "TSC_B") (class "Default")
      (node (ref "S2") (pin "4") (pinfunction "4_4") (pintype "passive"))
      (node (ref "U$2") (pin "17") (pinfunction "P$17_17") (pintype "bidirectional"))
    )
    (net (code "38") (name "UART_RX") (class "Default")
      (node (ref "RX") (pin "TP") (pinfunction "TP_TP") (pintype "input"))
      (node (ref "U$2") (pin "31") (pinfunction "P$31_31") (pintype "bidirectional"))
    )
    (net (code "39") (name "UART_TX") (class "Default")
      (node (ref "TX") (pin "TP") (pinfunction "TP_TP") (pintype "input"))
      (node (ref "U$2") (pin "30") (pinfunction "P$30_30") (pintype "bidirectional"))
    )
    (net (code "40") (name "unconnected-(S1-Pad1)") (class "Default")
      (node (ref "S1") (pin "1") (pinfunction "1_1") (pintype "passive"))
    )
    (net (code "41") (name "unconnected-(S1-Pad3)") (class "Default")
      (node (ref "S1") (pin "3") (pinfunction "3_3") (pintype "passive"))
    )
    (net (code "42") (name "unconnected-(S2-Pad1)") (class "Default")
      (node (ref "S2") (pin "1") (pinfunction "1_1") (pintype "passive"))
    )
    (net (code "43") (name "unconnected-(S2-Pad3)") (class "Default")
      (node (ref "S2") (pin "3") (pinfunction "3_3") (pintype "passive"))
    )
    (net (code "44") (name "unconnected-(S3-Pad1)") (class "Default")
      (node (ref "S3") (pin "1") (pinfunction "1_1") (pintype "passive"))
    )
    (net (code "45") (name "unconnected-(S3-Pad3)") (class "Default")
      (node (ref "S3") (pin "3") (pinfunction "3_3") (pintype "passive"))
    )
    (net (code "46") (name "unconnected-(S4-Pad1)") (class "Default")
      (node (ref "S4") (pin "1") (pinfunction "1_1") (pintype "passive"))
    )
    (net (code "47") (name "unconnected-(S4-Pad3)") (class "Default")
      (node (ref "S4") (pin "3") (pinfunction "3_3") (pintype "passive"))
    )
    (net (code "48") (name "unconnected-(S5-Pad1)") (class "Default")
      (node (ref "S5") (pin "1") (pinfunction "1_1") (pintype "passive"))
    )
    (net (code "49") (name "unconnected-(S5-Pad3)") (class "Default")
      (node (ref "S5") (pin "3") (pinfunction "3_3") (pintype "passive"))
    )
    (net (code "50") (name "unconnected-(S6-Pad1)") (class "Default")
      (node (ref "S6") (pin "1") (pinfunction "1_1") (pintype "passive"))
    )
    (net (code "51") (name "unconnected-(S6-Pad3)") (class "Default")
      (node (ref "S6") (pin "3") (pinfunction "3_3") (pintype "passive"))
    )
    (net (code "52") (name "unconnected-(U$2-P$1-Pad1)") (class "Default")
      (node (ref "U$2") (pin "1") (pinfunction "P$1_1") (pintype "bidirectional"))
    )
    (net (code "53") (name "unconnected-(U$2-P$2-Pad2)") (class "Default")
      (node (ref "U$2") (pin "2") (pinfunction "P$2_2") (pintype "bidirectional"))
    )
    (net (code "54") (name "unconnected-(U$2-P$3-Pad3)") (class "Default")
      (node (ref "U$2") (pin "3") (pinfunction "P$3_3") (pintype "bidirectional"))
    )
    (net (code "55") (name "unconnected-(U$2-P$4-Pad4)") (class "Default")
      (node (ref "U$2") (pin "4") (pinfunction "P$4_4") (pintype "bidirectional"))
    )
    (net (code "56") (name "unconnected-(U$2-P$5-Pad5)") (class "Default")
      (node (ref "U$2") (pin "5") (pinfunction "P$5_5") (pintype "bidirectional"))
    )
    (net (code "57") (name "unconnected-(U$2-P$6-Pad6)") (class "Default")
      (node (ref "U$2") (pin "6") (pinfunction "P$6_6") (pintype "bidirectional"))
    )
    (net (code "58") (name "unconnected-(U$2-P$10-Pad10)") (class "Default")
      (node (ref "U$2") (pin "10") (pinfunction "P$10_10") (pintype "bidirectional"))
    )
    (net (code "59") (name "unconnected-(U$2-P$14-Pad14)") (class "Default")
      (node (ref "U$2") (pin "14") (pinfunction "P$14_14") (pintype "bidirectional"))
    )
    (net (code "60") (name "unconnected-(U$2-P$29-Pad29)") (class "Default")
      (node (ref "U$2") (pin "29") (pinfunction "P$29_29") (pintype "bidirectional"))
    )
    (net (code "61") (name "unconnected-(U$2-P$32-Pad32)") (class "Default")
      (node (ref "U$2") (pin "32") (pinfunction "P$32_32") (pintype "bidirectional"))
    )
    (net (code "62") (name "unconnected-(U$2-P$33-Pad33)") (class "Default")
      (node (ref "U$2") (pin "33") (pinfunction "P$33_33") (pintype "bidirectional"))
    )
    (net (code "63") (name "unconnected-(U$2-P$35-Pad35)") (class "Default")
      (node (ref "U$2") (pin "35") (pinfunction "P$35_35") (pintype "bidirectional"))
    )
    (net (code "64") (name "unconnected-(U$2-P$36-Pad36)") (class "Default")
      (node (ref "U$2") (pin "36") (pinfunction "P$36_36") (pintype "bidirectional"))
    )
    (net (code "65") (name "unconnected-(U$2-P$38-Pad38)") (class "Default")
      (node (ref "U$2") (pin "38") (pinfunction "P$38_38") (pintype "bidirectional"))
    )
    (net (code "66") (name "unconnected-(U$12-O-Pad1)") (class "Default")
      (node (ref "U$12") (pin "1") (pinfunction "O_1") (pintype "passive"))
    )
  )
)
